# Buttons_LEDs_and_Connectors.net
KiCad netlist of a schematic drawn in Altium Designer
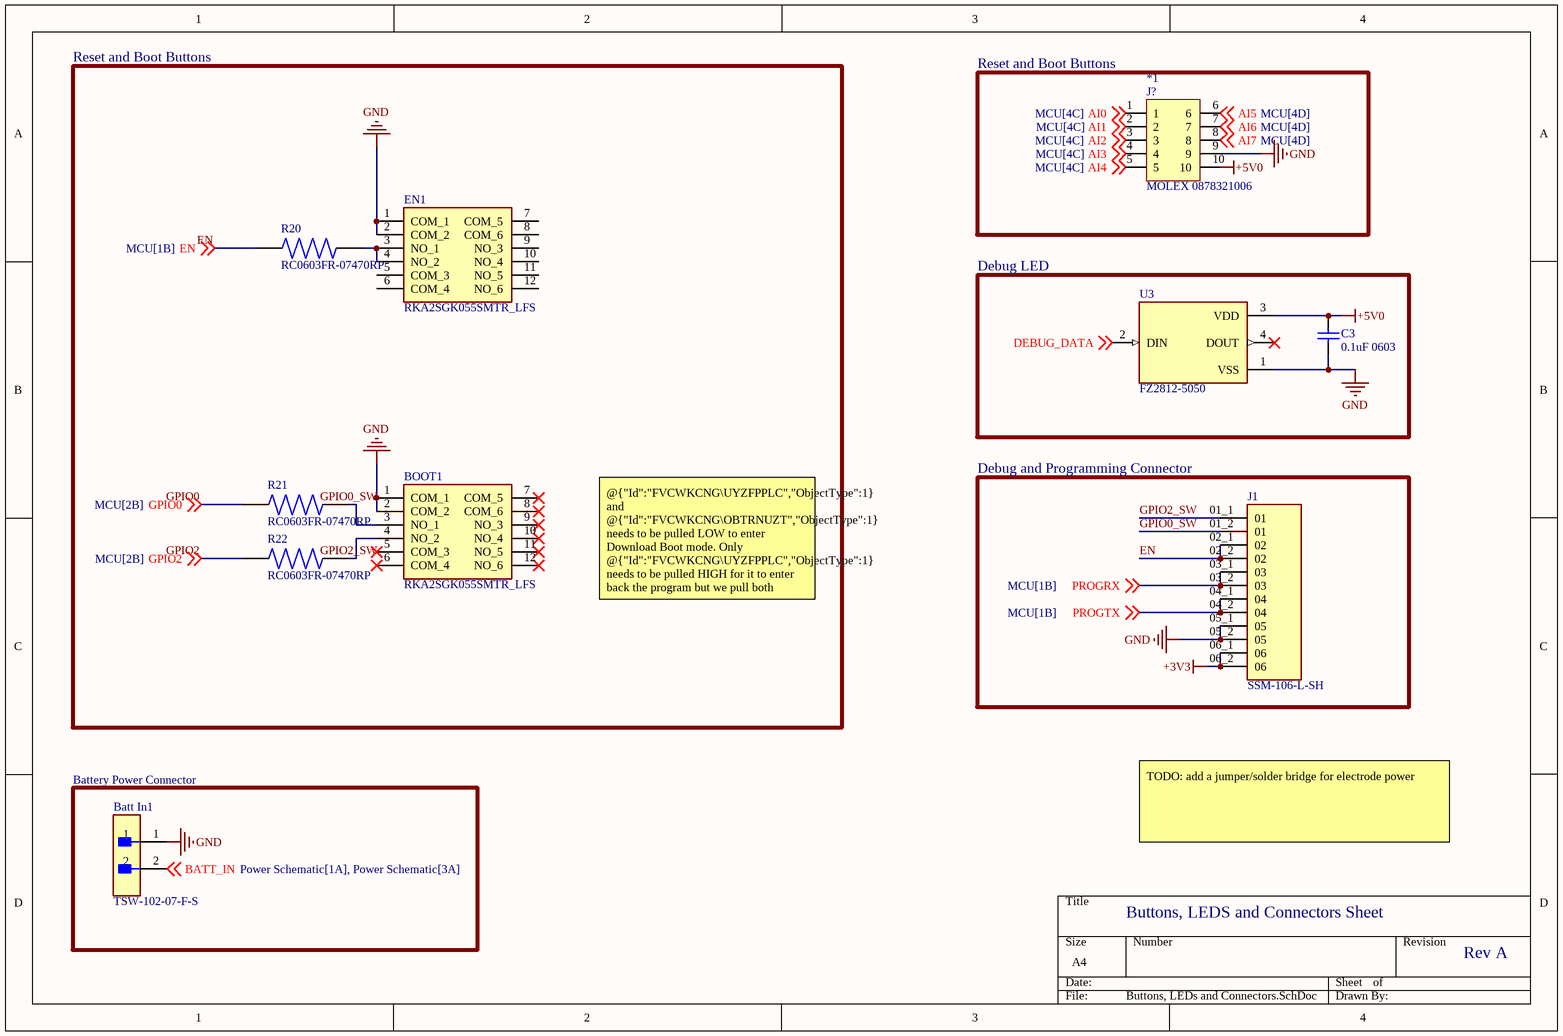
[diagram p0: Buttons, LEDs and Connectors.SchDoc]

(export (version "E")
  (design (tool "Eeschema 10.0.6"))
  (components
    (comp (ref "*1")
      (value "MOLEX 0878321006")
      (footprint "MOLEX 0878321006")
      (libsource (lib "Custom") (part "MOLEX 0878321006"))
    )
    (comp (ref "Batt In1")
      (value "TSW-102-07-F-S")
      (footprint "FP-TSW-102-07-F-S-MFG")
      (description "CONN HEADER VERT 2POS 2.54MM")
      (libsource (lib "Altium Content Vault") (part "3bc925449376181038e59eaffc5286c"))
    )
    (comp (ref "BOOT1")
      (value "RKA2SGK055SMTR_LFS")
      (footprint "SamacSys:RKA2SGK055SMTRLFS")
      (description "Switch")
      (fields
        (field (name "MANUFACTURER_PART_NUMBER") "RKA2SGK055SMTR LFS")
        (field (name "MOUSER PART NUMBER") "611-RKA2SGK055SMTRLF")
      )
      (libsource (lib "*") (part "RKA2SGK055SMTR_LFS"))
    )
    (comp (ref "C3")
      (value "0.1uF 0603")
      (footprint "CAPC1608X90X40LL10T20")
      (fields (field (name "TOLERANCE") "-20%,+80%") (field (name "MANUFACTURER") "Yageo"))
      (libsource (lib "Altium Content Vault") (part "CAP-NP-2"))
    )
    (comp (ref "EN1")
      (value "RKA2SGK055SMTR_LFS")
      (footprint "SamacSys:RKA2SGK055SMTRLFS")
      (description "Switch")
      (fields
        (field (name "MANUFACTURER_PART_NUMBER") "RKA2SGK055SMTR LFS")
        (field (name "MOUSER PART NUMBER") "611-RKA2SGK055SMTRLF")
      )
      (libsource (lib "*") (part "RKA2SGK055SMTR_LFS"))
    )
    (comp (ref "J1")
      (value "SSM-106-L-SH")
      (footprint "SSM-106-L-SH:SAMTEC_SSM-106-L-SH")
      (fields (field (name "MF") "{'manufacturer': u'Samtec'}"))
      (libsource (lib "*") (part "SSM-106-L-SH"))
    )
    (comp (ref "R20")
      (value "RC0603FR-07470RP")
      (footprint "RC0603FR07470RP:RESC1608X55N")
      (description "RES SMD 470 OHM 1% 1/10W 0603")
      (fields (field (name "MF") "{'manufacturer': u'Yageo Corporation'}"))
      (libsource (lib "*") (part "RC0603FR-07470RP"))
    )
    (comp (ref "R21")
      (value "RC0603FR-07470RP")
      (footprint "RC0603FR07470RP:RESC1608X55N")
      (description "RES SMD 470 OHM 1% 1/10W 0603")
      (fields (field (name "MF") "{'manufacturer': u'Yageo Corporation'}"))
      (libsource (lib "*") (part "RC0603FR-07470RP"))
    )
    (comp (ref "R22")
      (value "RC0603FR-07470RP")
      (footprint "RC0603FR07470RP:RESC1608X55N")
      (description "RES SMD 470 OHM 1% 1/10W 0603")
      (fields (field (name "MF") "{'manufacturer': u'Yageo Corporation'}"))
      (libsource (lib "*") (part "RC0603FR-07470RP"))
    )
    (comp (ref "U3")
      (value "FZ2812-5050")
      (footprint "FZ2812-5050:LED_FZ2812-5050")
      (fields (field (name "MF") "{'manufacturer': u'Feztek'}"))
      (libsource (lib "*") (part "FZ2812-5050"))
    )
  )
  (nets
    (net (code "1") (name "+3V3") (class "Default")
      (node (ref "J1") (pin "06_1") (pinfunction "06_06_1") (pintype "passive"))
      (node (ref "J1") (pin "06_2") (pinfunction "06_06_2") (pintype "passive"))
    )
    (net (code "2") (name "+5V0") (class "Default")
      (node (ref "*1") (pin "10") (pinfunction "10_10") (pintype "passive"))
      (node (ref "C3") (pin "2") (pinfunction "2_2") (pintype "passive"))
      (node (ref "U3") (pin "3") (pinfunction "VDD_3") (pintype "power_in"))
    )
    (net (code "3") (name "/GPIO0_SW") (class "Default")
      (node (ref "BOOT1") (pin "3") (pinfunction "NO_1_3") (pintype "passive"))
      (node (ref "J1") (pin "01_2") (pinfunction "01_01_2") (pintype "passive"))
      (node (ref "R21") (pin "1") (pinfunction "1_1") (pintype "passive"))
    )
    (net (code "4") (name "/GPIO2_SW") (class "Default")
      (node (ref "BOOT1") (pin "4") (pinfunction "NO_2_4") (pintype "passive"))
      (node (ref "J1") (pin "01_1") (pinfunction "01_01_1") (pintype "passive"))
      (node (ref "R22") (pin "1") (pinfunction "1_1") (pintype "passive"))
    )
    (net (code "5") (name "AI0") (class "Default")
      (node (ref "*1") (pin "1") (pinfunction "1_1") (pintype "passive"))
    )
    (net (code "6") (name "AI1") (class "Default")
      (node (ref "*1") (pin "2") (pinfunction "2_2") (pintype "passive"))
    )
    (net (code "7") (name "AI2") (class "Default")
      (node (ref "*1") (pin "3") (pinfunction "3_3") (pintype "passive"))
    )
    (net (code "8") (name "AI3") (class "Default")
      (node (ref "*1") (pin "4") (pinfunction "4_4") (pintype "passive"))
    )
    (net (code "9") (name "AI4") (class "Default")
      (node (ref "*1") (pin "5") (pinfunction "5_5") (pintype "passive"))
    )
    (net (code "10") (name "AI5") (class "Default")
      (node (ref "*1") (pin "6") (pinfunction "6_6") (pintype "passive"))
    )
    (net (code "11") (name "AI6") (class "Default")
      (node (ref "*1") (pin "7") (pinfunction "7_7") (pintype "passive"))
    )
    (net (code "12") (name "AI7") (class "Default")
      (node (ref "*1") (pin "8") (pinfunction "8_8") (pintype "passive"))
    )
    (net (code "13") (name "BATT_IN") (class "Default")
      (node (ref "Batt In1") (pin "2") (pinfunction "2_2") (pintype "passive"))
    )
    (net (code "14") (name "DEBUG_DATA") (class "Default")
      (node (ref "U3") (pin "2") (pinfunction "DIN_2") (pintype "input"))
    )
    (net (code "15") (name "EN") (class "Default")
      (node (ref "J1") (pin "02_1") (pinfunction "02_02_1") (pintype "passive"))
      (node (ref "J1") (pin "02_2") (pinfunction "02_02_2") (pintype "passive"))
      (node (ref "R20") (pin "2") (pinfunction "2_2") (pintype "passive"))
    )
    (net (code "16") (name "GND") (class "Default")
      (node (ref "*1") (pin "9") (pinfunction "9_9") (pintype "passive"))
      (node (ref "BOOT1") (pin "1") (pinfunction "COM_1_1") (pintype "passive"))
      (node (ref "BOOT1") (pin "2") (pinfunction "COM_2_2") (pintype "passive"))
      (node (ref "Batt In1") (pin "1") (pinfunction "1_1") (pintype "passive"))
      (node (ref "C3") (pin "1") (pinfunction "1_1") (pintype "passive"))
      (node (ref "EN1") (pin "1") (pinfunction "COM_1_1") (pintype "passive"))
      (node (ref "EN1") (pin "2") (pinfunction "COM_2_2") (pintype "passive"))
      (node (ref "J1") (pin "05_1") (pinfunction "05_05_1") (pintype "passive"))
      (node (ref "J1") (pin "05_2") (pinfunction "05_05_2") (pintype "passive"))
      (node (ref "U3") (pin "1") (pinfunction "VSS_1") (pintype "power_in"))
    )
    (net (code "17") (name "GPIO0") (class "Default")
      (node (ref "R21") (pin "2") (pinfunction "2_2") (pintype "passive"))
    )
    (net (code "18") (name "GPIO2") (class "Default")
      (node (ref "R22") (pin "2") (pinfunction "2_2") (pintype "passive"))
    )
    (net (code "19") (name "Net-(EN1-NO_1)") (class "Default")
      (node (ref "EN1") (pin "3") (pinfunction "NO_1_3") (pintype "passive"))
      (node (ref "EN1") (pin "4") (pinfunction "NO_2_4") (pintype "passive"))
      (node (ref "R20") (pin "1") (pinfunction "1_1") (pintype "passive"))
    )
    (net (code "20") (name "PROGRX") (class "Default")
      (node (ref "J1") (pin "03_1") (pinfunction "03_03_1") (pintype "passive"))
      (node (ref "J1") (pin "03_2") (pinfunction "03_03_2") (pintype "passive"))
    )
    (net (code "21") (name "PROGTX") (class "Default")
      (node (ref "J1") (pin "04_1") (pinfunction "04_04_1") (pintype "passive"))
      (node (ref "J1") (pin "04_2") (pinfunction "04_04_2") (pintype "passive"))
    )
    (net (code "22") (name "unconnected-(BOOT1-COM_3-Pad5)") (class "Default")
      (node (ref "BOOT1") (pin "5") (pinfunction "COM_3_5") (pintype "passive+no_connect"))
    )
    (net (code "23") (name "unconnected-(BOOT1-COM_4-Pad6)") (class "Default")
      (node (ref "BOOT1") (pin "6") (pinfunction "COM_4_6") (pintype "passive+no_connect"))
    )
    (net (code "24") (name "unconnected-(BOOT1-COM_5-Pad7)") (class "Default")
      (node (ref "BOOT1") (pin "7") (pinfunction "COM_5_7") (pintype "passive+no_connect"))
    )
    (net (code "25") (name "unconnected-(BOOT1-COM_6-Pad8)") (class "Default")
      (node (ref "BOOT1") (pin "8") (pinfunction "COM_6_8") (pintype "passive+no_connect"))
    )
    (net (code "26") (name "unconnected-(BOOT1-NO_3-Pad9)") (class "Default")
      (node (ref "BOOT1") (pin "9") (pinfunction "NO_3_9") (pintype "passive+no_connect"))
    )
    (net (code "27") (name "unconnected-(BOOT1-NO_4-Pad10)") (class "Default")
      (node (ref "BOOT1") (pin "10") (pinfunction "NO_4_10") (pintype "passive+no_connect"))
    )
    (net (code "28") (name "unconnected-(BOOT1-NO_5-Pad11)") (class "Default")
      (node (ref "BOOT1") (pin "11") (pinfunction "NO_5_11") (pintype "passive+no_connect"))
    )
    (net (code "29") (name "unconnected-(BOOT1-NO_6-Pad12)") (class "Default")
      (node (ref "BOOT1") (pin "12") (pinfunction "NO_6_12") (pintype "passive+no_connect"))
    )
    (net (code "30") (name "unconnected-(EN1-COM_3-Pad5)") (class "Default")
      (node (ref "EN1") (pin "5") (pinfunction "COM_3_5") (pintype "passive"))
    )
    (net (code "31") (name "unconnected-(EN1-COM_4-Pad6)") (class "Default")
      (node (ref "EN1") (pin "6") (pinfunction "COM_4_6") (pintype "passive"))
    )
    (net (code "32") (name "unconnected-(EN1-COM_5-Pad7)") (class "Default")
      (node (ref "EN1") (pin "7") (pinfunction "COM_5_7") (pintype "passive"))
    )
    (net (code "33") (name "unconnected-(EN1-COM_6-Pad8)") (class "Default")
      (node (ref "EN1") (pin "8") (pinfunction "COM_6_8") (pintype "passive"))
    )
    (net (code "34") (name "unconnected-(EN1-NO_3-Pad9)") (class "Default")
      (node (ref "EN1") (pin "9") (pinfunction "NO_3_9") (pintype "passive"))
    )
    (net (code "35") (name "unconnected-(EN1-NO_4-Pad10)") (class "Default")
      (node (ref "EN1") (pin "10") (pinfunction "NO_4_10") (pintype "passive"))
    )
    (net (code "36") (name "unconnected-(EN1-NO_5-Pad11)") (class "Default")
      (node (ref "EN1") (pin "11") (pinfunction "NO_5_11") (pintype "passive"))
    )
    (net (code "37") (name "unconnected-(EN1-NO_6-Pad12)") (class "Default")
      (node (ref "EN1") (pin "12") (pinfunction "NO_6_12") (pintype "passive"))
    )
    (net (code "38") (name "unconnected-(U3-DOUT-Pad4)") (class "Default")
      (node (ref "U3") (pin "4") (pinfunction "DOUT_4") (pintype "output+no_connect"))
    )
  )
)
